# RollerShutterNode_rfm69.net
KiCad netlist of a schematic drawn in EAGLE
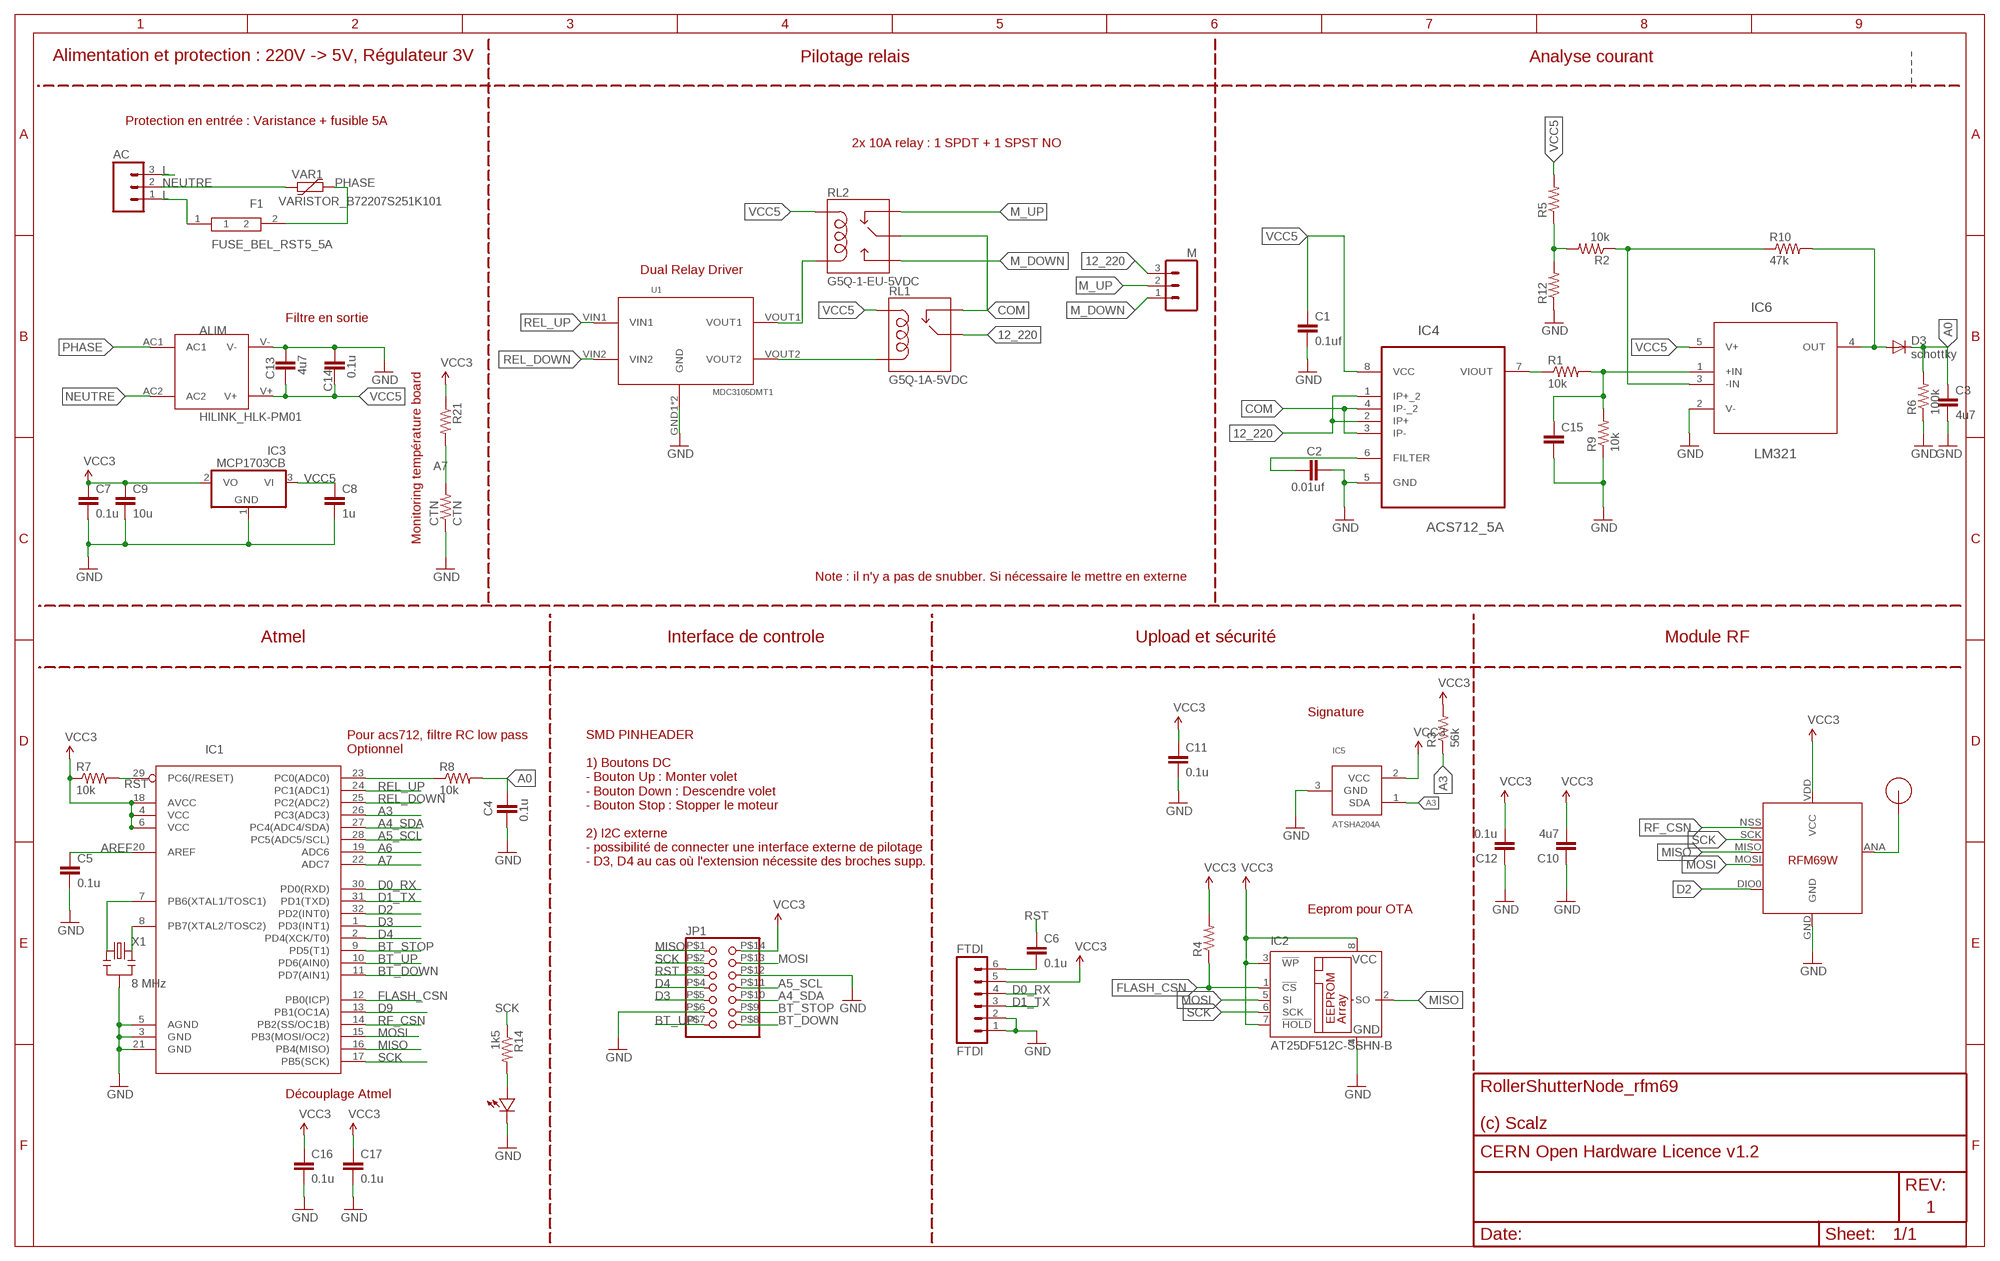
[diagram p0: schematic, sheet 1]

(export (version "E")
  (design (tool "Eeschema 10.0.6"))
  (components
    (comp (ref "AC")
      (value "M03-SCREW-5MM")
      (footprint "eagle-import:SCREWTERMINAL-5MM-3")
      (libsource (lib "eagle-import") (part "M03-SCREW-5MM"))
    )
    (comp (ref "ALIM")
      (value "HILINK_HLK-PM01")
      (footprint "eagle-import:HILINK_HLK-PM01")
      (libsource (lib "eagle-import") (part "HILINK_HLK-PM01"))
    )
    (comp (ref "ANT")
      (value "RFM12B_ANTENNA")
      (footprint "eagle-import:RFM12B-ANTENNA")
      (libsource (lib "eagle-import") (part "RFM12B_ANTENNA"))
    )
    (comp (ref "C1")
      (value "0.1uf")
      (footprint "eagle-import:0805-CAP")
      (libsource (lib "eagle-import") (part "CAP0805-CAP"))
    )
    (comp (ref "C2")
      (value "0.01uf")
      (footprint "eagle-import:0805-CAP")
      (libsource (lib "eagle-import") (part "CAP0805-CAP"))
    )
    (comp (ref "C3")
      (value "4u7")
      (footprint "eagle-import:0805-CAP")
      (libsource (lib "eagle-import") (part "CAP0805-CAP"))
    )
    (comp (ref "C4")
      (value "0.1u")
      (footprint "eagle-import:0805-CAP")
      (libsource (lib "eagle-import") (part "CAP0805-CAP"))
    )
    (comp (ref "C5")
      (value "0.1u")
      (footprint "eagle-import:0805-CAP")
      (libsource (lib "eagle-import") (part "CAP0805-CAP"))
    )
    (comp (ref "C6")
      (value "0.1u")
      (footprint "eagle-import:0805-CAP")
      (libsource (lib "eagle-import") (part "CAP0805-CAP"))
    )
    (comp (ref "C7")
      (value "0.1u")
      (footprint "eagle-import:0805-CAP")
      (libsource (lib "eagle-import") (part "CAP0805-CAP"))
    )
    (comp (ref "C8")
      (value "1u")
      (footprint "eagle-import:0805-CAP")
      (libsource (lib "eagle-import") (part "CAP0805-CAP"))
    )
    (comp (ref "C9")
      (value "10u")
      (footprint "eagle-import:0805-CAP")
      (libsource (lib "eagle-import") (part "CAP0805-CAP"))
    )
    (comp (ref "C10")
      (value "4u7")
      (footprint "eagle-import:0805-CAP")
      (libsource (lib "eagle-import") (part "CAP0805-CAP"))
    )
    (comp (ref "C11")
      (value "0.1u")
      (footprint "eagle-import:0805-CAP")
      (libsource (lib "eagle-import") (part "CAP0805-CAP"))
    )
    (comp (ref "C12")
      (value "0.1u")
      (footprint "eagle-import:0805-CAP")
      (libsource (lib "eagle-import") (part "CAP0805-CAP"))
    )
    (comp (ref "C13")
      (value "4u7")
      (footprint "eagle-import:0805-CAP")
      (libsource (lib "eagle-import") (part "CAP0805-CAP"))
    )
    (comp (ref "C14")
      (value "0.1u")
      (footprint "eagle-import:0805-CAP")
      (libsource (lib "eagle-import") (part "CAP0805-CAP"))
    )
    (comp (ref "C15")
      (value "CAP0805-CAP")
      (footprint "eagle-import:0805-CAP")
      (libsource (lib "eagle-import") (part "CAP0805-CAP"))
    )
    (comp (ref "C16")
      (value "0.1u")
      (footprint "eagle-import:0805-CAP")
      (libsource (lib "eagle-import") (part "CAP0805-CAP"))
    )
    (comp (ref "C17")
      (value "0.1u")
      (footprint "eagle-import:0805-CAP")
      (libsource (lib "eagle-import") (part "CAP0805-CAP"))
    )
    (comp (ref "CTN")
      (value "CTN")
      (footprint "eagle-import:0805-RES")
      (libsource (lib "eagle-import") (part "RESISTOR0805-RES"))
    )
    (comp (ref "D3")
      (value "schottky")
      (footprint "eagle-import:SOD-323")
      (libsource (lib "eagle-import") (part "DIODESOD"))
    )
    (comp (ref "D4")
      (value "LED0805")
      (footprint "eagle-import:0805-LED")
      (libsource (lib "eagle-import") (part "LED0805"))
    )
    (comp (ref "F1")
      (value "FUSE_BEL_RST5_5A")
      (footprint "eagle-import:FUSE_BEL_RST5_5A")
      (libsource (lib "eagle-import") (part "FUSE_BEL_RST5_5A"))
    )
    (comp (ref "FTDI")
      (value "FTDI")
      (footprint "eagle-import:1X06")
      (libsource (lib "eagle-import") (part "M06SIP"))
    )
    (comp (ref "IC1")
      (value "ATMega-328")
      (footprint "eagle-import:TQFP32-08")
      (libsource (lib "eagle-import") (part "ATMEGA168/328TQFP32"))
    )
    (comp (ref "IC2")
      (value "AT25DF512C-SSHN-B")
      (footprint "eagle-import:SO-08")
      (fields (field (name "MF") "MICROCHIP") (field (name "MPN") "25AA080/SN"))
      (libsource (lib "eagle-import") (part "25SNAA080"))
    )
    (comp (ref "IC3")
      (value "MCP1703CB")
      (footprint "eagle-import:SOT23")
      (libsource (lib "eagle-import") (part "MCP1703CB"))
    )
    (comp (ref "IC4")
      (value "ACS712_5A")
      (footprint "eagle-import:SOIC127P600X175-8N")
      (fields (field (name "MPN") "ACS712ELCTR-20A-T"))
      (libsource (lib "eagle-import") (part "ACS712ELCTR-20A-T"))
    )
    (comp (ref "IC5")
      (value "ATSHA204A")
      (footprint "eagle-import:SOT23")
      (libsource (lib "eagle-import") (part "ATSHA204A"))
    )
    (comp (ref "IC6")
      (value "LM321")
      (footprint "eagle-import:SOT95P285X120-5N")
      (fields (field (name "MPN") "LM321MF"))
      (libsource (lib "eagle-import") (part "LM321MF"))
    )
    (comp (ref "JP1")
      (value "PINHD-2X7")
      (footprint "eagle-import:2X07")
      (libsource (lib "eagle-import") (part "PINHD-2X7"))
    )
    (comp (ref "M")
      (value "M03-SCREW-5MM")
      (footprint "eagle-import:SCREWTERMINAL-5MM-3")
      (libsource (lib "eagle-import") (part "M03-SCREW-5MM"))
    )
    (comp (ref "R1")
      (value "10k")
      (footprint "eagle-import:0805-RES")
      (libsource (lib "eagle-import") (part "RESISTOR0805-RES"))
    )
    (comp (ref "R2")
      (value "10k")
      (footprint "eagle-import:0805-RES")
      (libsource (lib "eagle-import") (part "RESISTOR0805-RES"))
    )
    (comp (ref "R3")
      (value "56k")
      (footprint "eagle-import:0805-RES")
      (libsource (lib "eagle-import") (part "RESISTOR0805-RES"))
    )
    (comp (ref "R4")
      (value "RESISTOR0805-RES")
      (footprint "eagle-import:0805-RES")
      (libsource (lib "eagle-import") (part "RESISTOR0805-RES"))
    )
    (comp (ref "R5")
      (value "RESISTOR0805-RES")
      (footprint "eagle-import:0805-RES")
      (libsource (lib "eagle-import") (part "RESISTOR0805-RES"))
    )
    (comp (ref "R6")
      (value "100k")
      (footprint "eagle-import:0805-RES")
      (libsource (lib "eagle-import") (part "RESISTOR0805-RES"))
    )
    (comp (ref "R7")
      (value "10k")
      (footprint "eagle-import:0805-RES")
      (libsource (lib "eagle-import") (part "RESISTOR0805-RES"))
    )
    (comp (ref "R8")
      (value "10k")
      (footprint "eagle-import:0805-RES")
      (libsource (lib "eagle-import") (part "RESISTOR0805-RES"))
    )
    (comp (ref "R9")
      (value "10k")
      (footprint "eagle-import:0805-RES")
      (libsource (lib "eagle-import") (part "RESISTOR0805-RES"))
    )
    (comp (ref "R10")
      (value "47k")
      (footprint "eagle-import:0805-RES")
      (libsource (lib "eagle-import") (part "RESISTOR0805-RES"))
    )
    (comp (ref "R12")
      (value "RESISTOR0805-RES")
      (footprint "eagle-import:0805-RES")
      (libsource (lib "eagle-import") (part "RESISTOR0805-RES"))
    )
    (comp (ref "R14")
      (value "1k5")
      (footprint "eagle-import:0805-RES")
      (libsource (lib "eagle-import") (part "RESISTOR0805-RES"))
    )
    (comp (ref "R21")
      (value "RESISTOR0805-RES")
      (footprint "eagle-import:0805-RES")
      (libsource (lib "eagle-import") (part "RESISTOR0805-RES"))
    )
    (comp (ref "RFM69")
      (value "RFM69")
      (footprint "eagle-import:RFM69W-MINPADS")
      (libsource (lib "eagle-import") (part "RFM69"))
    )
    (comp (ref "RL1")
      (value "G5Q-1A-5VDC")
      (footprint "eagle-import:G5Q_SINGLE")
      (libsource (lib "eagle-import") (part "G5Q_SINGLE"))
    )
    (comp (ref "RL2")
      (value "G5Q-1-EU-5VDC")
      (footprint "eagle-import:RELAY-G5Q")
      (libsource (lib "eagle-import") (part "RELAYPTH"))
    )
    (comp (ref "U1")
      (value "MDC3105DMT1")
      (footprint "eagle-import:MDC3105DMT1")
      (libsource (lib "eagle-import") (part "MDC3105DMT1"))
    )
    (comp (ref "VAR1")
      (value "VARISTOR_B72207S251K101")
      (footprint "eagle-import:VARISTOR_B72207S251K101")
      (libsource (lib "eagle-import") (part "VARISTOR_B72207S251K101"))
    )
    (comp (ref "X1")
      (value "8 MHz")
      (footprint "eagle-import:RESONATOR-SMD")
      (libsource (lib "eagle-import") (part "RESONATORSMD"))
    )
  )
  (nets
    (net (code "1") (name "/A4_SDA") (class "Default")
      (node (ref "IC1") (pin "27") (pinfunction "PC4(ADC4/SDA)_27") (pintype "bidirectional"))
      (node (ref "JP1") (pin "P$10") (pinfunction "10_P$10") (pintype "passive"))
    )
    (net (code "2") (name "/A5_SCL") (class "Default")
      (node (ref "IC1") (pin "28") (pinfunction "PC5(ADC5/SCL)_28") (pintype "bidirectional"))
      (node (ref "JP1") (pin "P$11") (pinfunction "8_P$11") (pintype "passive"))
    )
    (net (code "3") (name "/A6") (class "Default")
      (node (ref "IC1") (pin "19") (pinfunction "ADC6_19") (pintype "bidirectional"))
    )
    (net (code "4") (name "/A7") (class "Default")
      (node (ref "CTN") (pin "2") (pinfunction "2_2") (pintype "passive"))
      (node (ref "IC1") (pin "22") (pinfunction "ADC7_22") (pintype "bidirectional"))
      (node (ref "R21") (pin "2") (pinfunction "2_2") (pintype "passive"))
    )
    (net (code "5") (name "/AREF") (class "Default")
      (node (ref "C5") (pin "1") (pinfunction "1_1") (pintype "passive"))
      (node (ref "IC1") (pin "20") (pinfunction "AREF_20") (pintype "bidirectional"))
    )
    (net (code "6") (name "/BT_DOWN") (class "Default")
      (node (ref "IC1") (pin "11") (pinfunction "PD7(AIN1)_11") (pintype "bidirectional"))
      (node (ref "JP1") (pin "P$8") (pinfunction "14_P$8") (pintype "passive"))
    )
    (net (code "7") (name "/BT_STOP") (class "Default")
      (node (ref "IC1") (pin "9") (pinfunction "PD5(T1)_9") (pintype "bidirectional"))
      (node (ref "JP1") (pin "P$9") (pinfunction "12_P$9") (pintype "passive"))
    )
    (net (code "8") (name "/BT_UP") (class "Default")
      (node (ref "IC1") (pin "10") (pinfunction "PD6(AIN0)_10") (pintype "bidirectional"))
      (node (ref "JP1") (pin "P$7") (pinfunction "13_P$7") (pintype "passive"))
    )
    (net (code "9") (name "/D0_RX") (class "Default")
      (node (ref "FTDI") (pin "4") (pinfunction "4_4") (pintype "passive"))
      (node (ref "IC1") (pin "30") (pinfunction "PD0(RXD)_30") (pintype "bidirectional"))
    )
    (net (code "10") (name "/D1_TX") (class "Default")
      (node (ref "FTDI") (pin "3") (pinfunction "3_3") (pintype "passive"))
      (node (ref "IC1") (pin "31") (pinfunction "PD1(TXD)_31") (pintype "bidirectional"))
    )
    (net (code "11") (name "/D3") (class "Default")
      (node (ref "IC1") (pin "1") (pinfunction "PD3(INT1)_1") (pintype "bidirectional"))
      (node (ref "JP1") (pin "P$5") (pinfunction "9_P$5") (pintype "passive"))
    )
    (net (code "12") (name "/D4") (class "Default")
      (node (ref "IC1") (pin "2") (pinfunction "PD4(XCK/T0)_2") (pintype "bidirectional"))
      (node (ref "JP1") (pin "P$4") (pinfunction "7_P$4") (pintype "passive"))
    )
    (net (code "13") (name "/D9") (class "Default")
      (node (ref "IC1") (pin "13") (pinfunction "PB1(OC1A)_13") (pintype "bidirectional"))
    )
    (net (code "14") (name "/L") (class "Default")
      (node (ref "AC") (pin "1") (pinfunction "1_1") (pintype "passive"))
      (node (ref "AC") (pin "3") (pinfunction "3_3") (pintype "passive"))
      (node (ref "F1") (pin "1") (pinfunction "1_1") (pintype "bidirectional"))
    )
    (net (code "15") (name "/RST") (class "Default")
      (node (ref "C6") (pin "1") (pinfunction "1_1") (pintype "passive"))
      (node (ref "IC1") (pin "29") (pinfunction "PC6(/RESET)_29") (pintype "bidirectional"))
      (node (ref "JP1") (pin "P$3") (pinfunction "5_P$3") (pintype "passive"))
      (node (ref "R7") (pin "2") (pinfunction "2_2") (pintype "passive"))
    )
    (net (code "16") (name "12_220") (class "Default")
      (node (ref "IC4") (pin "1") (pinfunction "IP+_2_1") (pintype "input"))
      (node (ref "IC4") (pin "2") (pinfunction "IP+_2") (pintype "input"))
      (node (ref "M") (pin "3") (pinfunction "3_3") (pintype "passive"))
      (node (ref "RL1") (pin "2") (pinfunction "MAIN_2") (pintype "bidirectional"))
    )
    (net (code "17") (name "A0") (class "Default")
      (node (ref "C3") (pin "1") (pinfunction "1_1") (pintype "passive"))
      (node (ref "C4") (pin "2") (pinfunction "2_2") (pintype "passive"))
      (node (ref "D3") (pin "1") (pinfunction "C_1") (pintype "passive"))
      (node (ref "R6") (pin "2") (pinfunction "2_2") (pintype "passive"))
      (node (ref "R8") (pin "2") (pinfunction "2_2") (pintype "passive"))
    )
    (net (code "18") (name "A3") (class "Default")
      (node (ref "IC1") (pin "26") (pinfunction "PC3(ADC3)_26") (pintype "bidirectional"))
      (node (ref "IC5") (pin "1") (pinfunction "SDA_1") (pintype "bidirectional"))
      (node (ref "R3") (pin "1") (pinfunction "1_1") (pintype "passive"))
    )
    (net (code "19") (name "COM") (class "Default")
      (node (ref "IC4") (pin "3") (pinfunction "IP-_3") (pintype "input"))
      (node (ref "IC4") (pin "4") (pinfunction "IP-_2_4") (pintype "input"))
      (node (ref "RL1") (pin "3") (pinfunction "NC_3") (pintype "bidirectional"))
      (node (ref "RL2") (pin "2") (pinfunction "MAIN_2") (pintype "bidirectional"))
    )
    (net (code "20") (name "D2") (class "Default")
      (node (ref "IC1") (pin "32") (pinfunction "PD2(INT0)_32") (pintype "bidirectional"))
      (node (ref "RFM69") (pin "DIO0") (pinfunction "DIO0_DIO0") (pintype "open_collector"))
    )
    (net (code "21") (name "FLASH_CSN") (class "Default")
      (node (ref "IC1") (pin "12") (pinfunction "PB0(ICP)_12") (pintype "bidirectional"))
      (node (ref "IC2") (pin "1") (pinfunction "~{CS}_1") (pintype "input"))
      (node (ref "R4") (pin "1") (pinfunction "1_1") (pintype "passive"))
    )
    (net (code "22") (name "GND") (class "Default")
      (node (ref "ALIM") (pin "V-") (pinfunction "V-_V-") (pintype "bidirectional"))
      (node (ref "C1") (pin "2") (pinfunction "2_2") (pintype "passive"))
      (node (ref "C10") (pin "1") (pinfunction "1_1") (pintype "passive"))
      (node (ref "C11") (pin "2") (pinfunction "2_2") (pintype "passive"))
      (node (ref "C12") (pin "1") (pinfunction "1_1") (pintype "passive"))
      (node (ref "C13") (pin "2") (pinfunction "2_2") (pintype "passive"))
      (node (ref "C14") (pin "2") (pinfunction "2_2") (pintype "passive"))
      (node (ref "C15") (pin "2") (pinfunction "2_2") (pintype "passive"))
      (node (ref "C16") (pin "2") (pinfunction "2_2") (pintype "passive"))
      (node (ref "C17") (pin "2") (pinfunction "2_2") (pintype "passive"))
      (node (ref "C2") (pin "2") (pinfunction "2_2") (pintype "passive"))
      (node (ref "C3") (pin "2") (pinfunction "2_2") (pintype "passive"))
      (node (ref "C4") (pin "1") (pinfunction "1_1") (pintype "passive"))
      (node (ref "C5") (pin "2") (pinfunction "2_2") (pintype "passive"))
      (node (ref "C7") (pin "2") (pinfunction "2_2") (pintype "passive"))
      (node (ref "C8") (pin "2") (pinfunction "2_2") (pintype "passive"))
      (node (ref "C9") (pin "2") (pinfunction "2_2") (pintype "passive"))
      (node (ref "CTN") (pin "1") (pinfunction "1_1") (pintype "passive"))
      (node (ref "D4") (pin "MINUS") (pinfunction "MINUS_MINUS") (pintype "passive"))
      (node (ref "FTDI") (pin "1") (pinfunction "1_1") (pintype "passive"))
      (node (ref "FTDI") (pin "2") (pinfunction "2_2") (pintype "passive"))
      (node (ref "IC1") (pin "21") (pinfunction "GND_21") (pintype "bidirectional"))
      (node (ref "IC1") (pin "3") (pinfunction "GND_3") (pintype "bidirectional"))
      (node (ref "IC1") (pin "5") (pinfunction "AGND_5") (pintype "bidirectional"))
      (node (ref "IC2") (pin "4") (pinfunction "GND_4") (pintype "power_in"))
      (node (ref "IC3") (pin "1") (pinfunction "GND_1") (pintype "passive"))
      (node (ref "IC4") (pin "5") (pinfunction "GND_5") (pintype "passive"))
      (node (ref "IC5") (pin "3") (pinfunction "GND_3") (pintype "bidirectional"))
      (node (ref "IC6") (pin "2") (pinfunction "V-_2") (pintype "power_in"))
      (node (ref "JP1") (pin "P$12") (pinfunction "6_P$12") (pintype "passive"))
      (node (ref "JP1") (pin "P$6") (pinfunction "11_P$6") (pintype "passive"))
      (node (ref "R12") (pin "1") (pinfunction "1_1") (pintype "passive"))
      (node (ref "R6") (pin "1") (pinfunction "1_1") (pintype "passive"))
      (node (ref "R9") (pin "1") (pinfunction "1_1") (pintype "passive"))
      (node (ref "RFM69") (pin "GND") (pinfunction "GND_GND") (pintype "power_in"))
      (node (ref "U1") (pin "GND1") (pinfunction "GND_GND1") (pintype "bidirectional"))
      (node (ref "U1") (pin "GND2") (pinfunction "GND_GND2") (pintype "bidirectional"))
      (node (ref "X1") (pin "2") (pinfunction "2_2") (pintype "passive"))
    )
    (net (code "23") (name "MISO") (class "Default")
      (node (ref "IC1") (pin "16") (pinfunction "PB4(MISO)_16") (pintype "bidirectional"))
      (node (ref "IC2") (pin "2") (pinfunction "SO_2") (pintype "bidirectional"))
      (node (ref "JP1") (pin "P$1") (pinfunction "1_P$1") (pintype "passive"))
      (node (ref "RFM69") (pin "MISO") (pinfunction "MISO_MISO") (pintype "input"))
    )
    (net (code "24") (name "MOSI") (class "Default")
      (node (ref "IC1") (pin "15") (pinfunction "PB3(MOSI/OC2)_15") (pintype "bidirectional"))
      (node (ref "IC2") (pin "5") (pinfunction "SI_5") (pintype "input"))
      (node (ref "JP1") (pin "P$13") (pinfunction "4_P$13") (pintype "passive"))
      (node (ref "RFM69") (pin "MOSI") (pinfunction "MOSI_MOSI") (pintype "output"))
    )
    (net (code "25") (name "M_DOWN") (class "Default")
      (node (ref "M") (pin "1") (pinfunction "1_1") (pintype "passive"))
      (node (ref "RL2") (pin "3") (pinfunction "NO_3") (pintype "bidirectional"))
    )
    (net (code "26") (name "M_UP") (class "Default")
      (node (ref "M") (pin "2") (pinfunction "2_2") (pintype "passive"))
      (node (ref "RL2") (pin "4") (pinfunction "NC_4") (pintype "bidirectional"))
    )
    (net (code "27") (name "NEUTRE") (class "Default")
      (node (ref "AC") (pin "2") (pinfunction "2_2") (pintype "passive"))
      (node (ref "ALIM") (pin "AC2") (pinfunction "AC2_AC2") (pintype "bidirectional"))
      (node (ref "VAR1") (pin "1") (pinfunction "1_1") (pintype "passive"))
    )
    (net (code "28") (name "Net-(ANT-1)") (class "Default")
      (node (ref "ANT") (pin "P$1") (pinfunction "1_P$1") (pintype "bidirectional"))
      (node (ref "RFM69") (pin "ANA") (pinfunction "ANT_ANA") (pintype "passive"))
    )
    (net (code "29") (name "Net-(C6-Pad2)") (class "Default")
      (node (ref "C6") (pin "2") (pinfunction "2_2") (pintype "passive"))
      (node (ref "FTDI") (pin "6") (pinfunction "6_6") (pintype "passive"))
    )
    (net (code "30") (name "Net-(D3-A)") (class "Default")
      (node (ref "D3") (pin "2") (pinfunction "A_2") (pintype "passive"))
      (node (ref "IC6") (pin "4") (pinfunction "OUT_4") (pintype "output"))
      (node (ref "R10") (pin "2") (pinfunction "2_2") (pintype "passive"))
    )
    (net (code "31") (name "Net-(D4-PadPLUS)") (class "Default")
      (node (ref "D4") (pin "PLUS") (pinfunction "PLUS_PLUS") (pintype "passive"))
      (node (ref "R14") (pin "2") (pinfunction "2_2") (pintype "passive"))
    )
    (net (code "32") (name "Net-(IC1-PB6(XTAL1{slash}TOSC1))") (class "Default")
      (node (ref "IC1") (pin "7") (pinfunction "PB6(XTAL1/TOSC1)_7") (pintype "bidirectional"))
      (node (ref "X1") (pin "1") (pinfunction "1_1") (pintype "passive"))
    )
    (net (code "33") (name "Net-(IC1-PB7(XTAL2{slash}TOSC2))") (class "Default")
      (node (ref "IC1") (pin "8") (pinfunction "PB7(XTAL2/TOSC2)_8") (pintype "bidirectional"))
      (node (ref "X1") (pin "3") (pinfunction "3_3") (pintype "passive"))
    )
    (net (code "34") (name "Net-(IC1-PC0(ADC0))") (class "Default")
      (node (ref "IC1") (pin "23") (pinfunction "PC0(ADC0)_23") (pintype "bidirectional"))
      (node (ref "R8") (pin "1") (pinfunction "1_1") (pintype "passive"))
    )
    (net (code "35") (name "Net-(IC4-FILTER)") (class "Default")
      (node (ref "C2") (pin "1") (pinfunction "1_1") (pintype "passive"))
      (node (ref "IC4") (pin "6") (pinfunction "FILTER_6") (pintype "input"))
    )
    (net (code "36") (name "Net-(IC4-VIOUT)") (class "Default")
      (node (ref "IC4") (pin "7") (pinfunction "VIOUT_7") (pintype "output"))
      (node (ref "R1") (pin "1") (pinfunction "1_1") (pintype "passive"))
    )
    (net (code "37") (name "Net-(IC6-+IN)") (class "Default")
      (node (ref "C15") (pin "1") (pinfunction "1_1") (pintype "passive"))
      (node (ref "IC6") (pin "1") (pinfunction "+IN_1") (pintype "input"))
      (node (ref "R1") (pin "2") (pinfunction "2_2") (pintype "passive"))
      (node (ref "R9") (pin "2") (pinfunction "2_2") (pintype "passive"))
    )
    (net (code "38") (name "Net-(IC6--IN)") (class "Default")
      (node (ref "IC6") (pin "3") (pinfunction "-IN_3") (pintype "input"))
      (node (ref "R10") (pin "1") (pinfunction "1_1") (pintype "passive"))
      (node (ref "R2") (pin "1") (pinfunction "1_1") (pintype "passive"))
    )
    (net (code "39") (name "Net-(R12-Pad2)") (class "Default")
      (node (ref "R12") (pin "2") (pinfunction "2_2") (pintype "passive"))
      (node (ref "R2") (pin "2") (pinfunction "2_2") (pintype "passive"))
      (node (ref "R5") (pin "1") (pinfunction "1_1") (pintype "passive"))
    )
    (net (code "40") (name "Net-(RL1-COIL2)") (class "Default")
      (node (ref "RL1") (pin "5") (pinfunction "COIL2_5") (pintype "bidirectional"))
      (node (ref "U1") (pin "VOUT2") (pinfunction "VOUT2_VOUT2") (pintype "bidirectional"))
    )
    (net (code "41") (name "Net-(RL2-COIL2)") (class "Default")
      (node (ref "RL2") (pin "1") (pinfunction "COIL2_1") (pintype "bidirectional"))
      (node (ref "U1") (pin "VOUT1") (pinfunction "VOUT1_VOUT1") (pintype "bidirectional"))
    )
    (net (code "42") (name "PHASE") (class "Default")
      (node (ref "ALIM") (pin "AC1") (pinfunction "AC1_AC1") (pintype "bidirectional"))
      (node (ref "F1") (pin "2") (pinfunction "2_2") (pintype "bidirectional"))
      (node (ref "VAR1") (pin "2") (pinfunction "2_2") (pintype "passive"))
    )
    (net (code "43") (name "REL_DOWN") (class "Default")
      (node (ref "IC1") (pin "25") (pinfunction "PC2(ADC2)_25") (pintype "bidirectional"))
      (node (ref "U1") (pin "VIN2") (pinfunction "VIN2_VIN2") (pintype "bidirectional"))
    )
    (net (code "44") (name "REL_UP") (class "Default")
      (node (ref "IC1") (pin "24") (pinfunction "PC1(ADC1)_24") (pintype "bidirectional"))
      (node (ref "U1") (pin "VIN1") (pinfunction "VIN1_VIN1") (pintype "bidirectional"))
    )
    (net (code "45") (name "RF_CSN") (class "Default")
      (node (ref "IC1") (pin "14") (pinfunction "PB2(SS/OC1B)_14") (pintype "bidirectional"))
      (node (ref "RFM69") (pin "NSS") (pinfunction "SEL_NSS") (pintype "input"))
    )
    (net (code "46") (name "SCK") (class "Default")
      (node (ref "IC1") (pin "17") (pinfunction "PB5(SCK)_17") (pintype "bidirectional"))
      (node (ref "IC2") (pin "6") (pinfunction "SCK_6") (pintype "input"))
      (node (ref "JP1") (pin "P$2") (pinfunction "3_P$2") (pintype "passive"))
      (node (ref "R14") (pin "1") (pinfunction "1_1") (pintype "passive"))
      (node (ref "RFM69") (pin "SCK") (pinfunction "SCK_SCK") (pintype "input"))
    )
    (net (code "47") (name "VCC3") (class "Default")
      (node (ref "C10") (pin "2") (pinfunction "2_2") (pintype "passive"))
      (node (ref "C11") (pin "1") (pinfunction "1_1") (pintype "passive"))
      (node (ref "C12") (pin "2") (pinfunction "2_2") (pintype "passive"))
      (node (ref "C16") (pin "1") (pinfunction "1_1") (pintype "passive"))
      (node (ref "C17") (pin "1") (pinfunction "1_1") (pintype "passive"))
      (node (ref "C7") (pin "1") (pinfunction "1_1") (pintype "passive"))
      (node (ref "C9") (pin "1") (pinfunction "1_1") (pintype "passive"))
      (node (ref "FTDI") (pin "5") (pinfunction "5_5") (pintype "passive"))
      (node (ref "IC1") (pin "18") (pinfunction "AVCC_18") (pintype "bidirectional"))
      (node (ref "IC1") (pin "4") (pinfunction "VCC_4") (pintype "bidirectional"))
      (node (ref "IC1") (pin "6") (pinfunction "VCC_6") (pintype "bidirectional"))
      (node (ref "IC2") (pin "3") (pinfunction "~{WP}_3") (pintype "input"))
      (node (ref "IC2") (pin "7") (pinfunction "~{HOLD}_7") (pintype "input"))
      (node (ref "IC2") (pin "8") (pinfunction "VCC_8") (pintype "power_in"))
      (node (ref "IC3") (pin "2") (pinfunction "VO_2") (pintype "passive"))
      (node (ref "IC5") (pin "2") (pinfunction "VCC_2") (pintype "bidirectional"))
      (node (ref "JP1") (pin "P$14") (pinfunction "2_P$14") (pintype "passive"))
      (node (ref "R21") (pin "1") (pinfunction "1_1") (pintype "passive"))
      (node (ref "R3") (pin "2") (pinfunction "2_2") (pintype "passive"))
      (node (ref "R4") (pin "2") (pinfunction "2_2") (pintype "passive"))
      (node (ref "R7") (pin "1") (pinfunction "1_1") (pintype "passive"))
      (node (ref "RFM69") (pin "VDD") (pinfunction "VCC_VDD") (pintype "power_in"))
    )
    (net (code "48") (name "VCC5") (class "Default")
      (node (ref "ALIM") (pin "V+") (pinfunction "V+_V+") (pintype "bidirectional"))
      (node (ref "C1") (pin "1") (pinfunction "1_1") (pintype "passive"))
      (node (ref "C13") (pin "1") (pinfunction "1_1") (pintype "passive"))
      (node (ref "C14") (pin "1") (pinfunction "1_1") (pintype "passive"))
      (node (ref "C8") (pin "1") (pinfunction "1_1") (pintype "passive"))
      (node (ref "IC3") (pin "3") (pinfunction "VI_3") (pintype "input"))
      (node (ref "IC4") (pin "8") (pinfunction "VCC_8") (pintype "power_in"))
      (node (ref "IC6") (pin "5") (pinfunction "V+_5") (pintype "power_in"))
      (node (ref "R5") (pin "2") (pinfunction "2_2") (pintype "passive"))
      (node (ref "RL1") (pin "1") (pinfunction "COIL1_1") (pintype "bidirectional"))
      (node (ref "RL2") (pin "5") (pinfunction "COIL1_5") (pintype "bidirectional"))
    )
  )
)
